# Power.net
KiCad netlist of a schematic drawn in Altium Designer
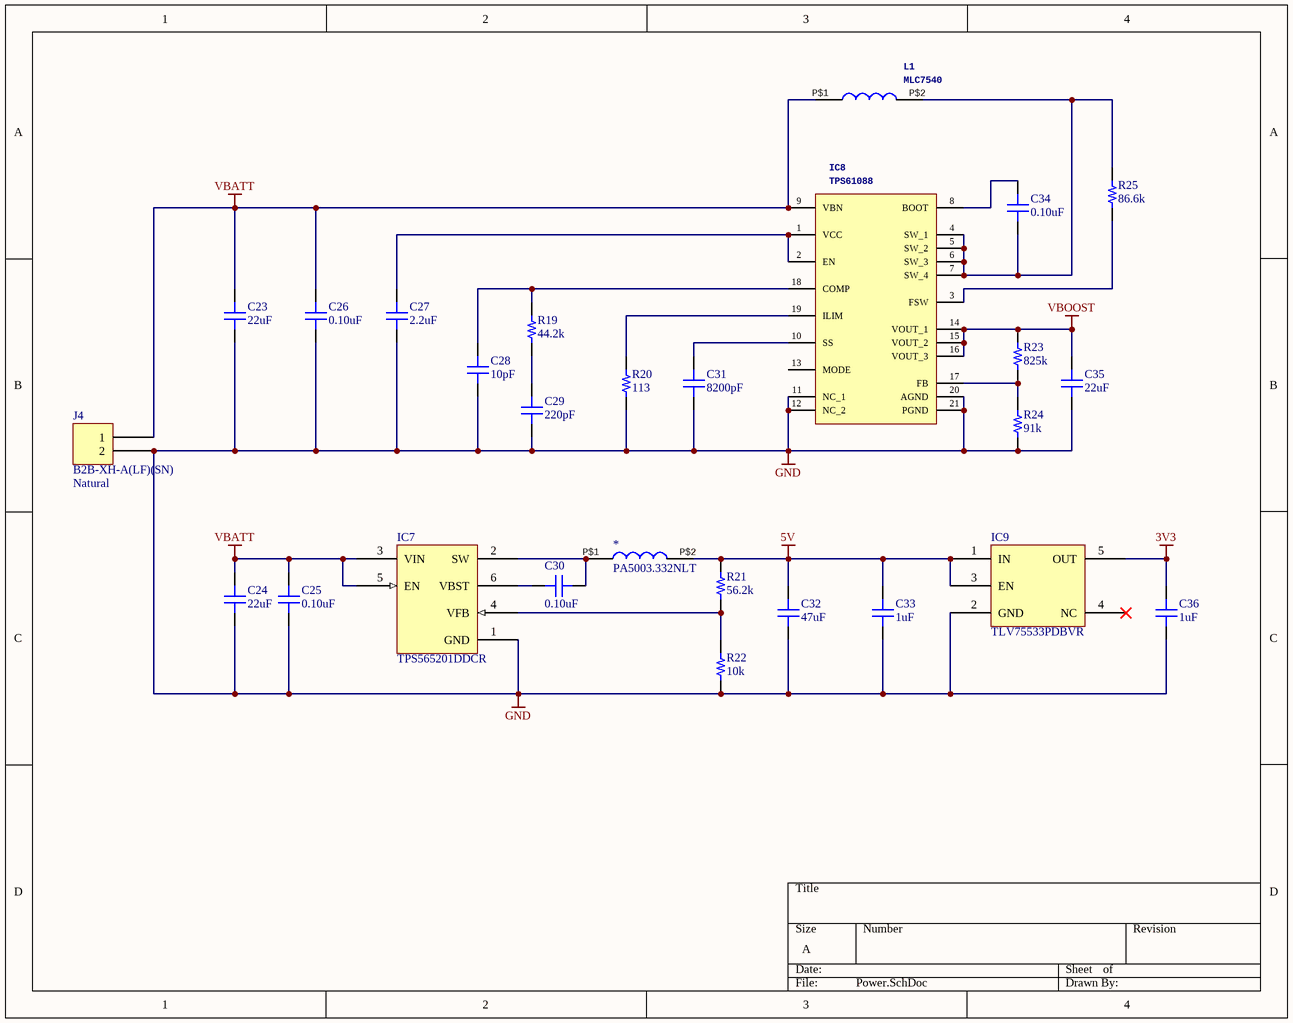
[diagram p0: Power.SchDoc]

(export (version "E")
  (design (tool "Eeschema 10.0.6"))
  (components
    (comp (ref "*")
      (value "PA5003.332NLT")
      (footprint "PA5003")
      (libsource (lib "micromousev2Parts") (part "PA5003.332NLT"))
    )
    (comp (ref "C23")
      (value "22uF")
      (footprint "CAP 1210/3225 - 2.8MM")
      (description "CAP CER 22UF 25V X7R 1210")
      (fields (field (name "PART NUMBER") "TMK325B7226KMHT") (field (name "MANUFACTURER") "Taiyo Yuden"))
      (libsource (lib "Celestial Library Database") (part "Capacitor"))
    )
    (comp (ref "C24")
      (value "22uF")
      (footprint "CAP 0805/2012")
      (description "CAP CER 22UF 16V X5R 0805")
      (fields
        (field (name "PART NUMBER") "CL21A226MOQNNNE")
        (field (name "MANUFACTURER") "Samsung Electro-Mechanics America, Inc.")
      )
      (libsource (lib "Celestial Library Database") (part "Capacitor"))
    )
    (comp (ref "C25")
      (value "0.10uF")
      (footprint "CAP 0402/1005")
      (description "CAP CER 0.1UF 10V X7R 0402")
      (fields
        (field (name "PART NUMBER") "GRM155R71A104KA01D")
        (field (name "MANUFACTURER") "Murata Electronics North America")
      )
      (libsource (lib "Celestial Library Database") (part "Capacitor"))
    )
    (comp (ref "C26")
      (value "0.10uF")
      (footprint "CAP 0603/1608")
      (description "CAP CER 0.1UF 16V X7R 0603")
      (fields (field (name "PART NUMBER") "C0603X104K4RACTU") (field (name "MANUFACTURER") "Kemet"))
      (libsource (lib "Celestial Library Database") (part "Capacitor"))
    )
    (comp (ref "C27")
      (value "2.2uF")
      (footprint "CAP 0603/1608")
      (description "CAP CER 2.2UF 35V X5R 0603")
      (fields
        (field (name "PART NUMBER") "C1608X5R1V225K080AC")
        (field (name "MANUFACTURER") "TDK Corporation")
      )
      (libsource (lib "Celestial Library Database") (part "Capacitor"))
    )
    (comp (ref "C28")
      (value "10pF")
      (footprint "CAP 0402/1005")
      (description "CAP CER 10PF 25V NP0 0402")
      (fields (field (name "PART NUMBER") "C0402C100J3GACTU") (field (name "MANUFACTURER") "Kemet"))
      (libsource (lib "Celestial Library Database") (part "Capacitor"))
    )
    (comp (ref "C29")
      (value "220pF")
      (footprint "CAP 0402/1005")
      (description "CAP CER 220PF 25V NPO 0402")
      (fields (field (name "PART NUMBER") "CC0402JRNPO8BN221") (field (name "MANUFACTURER") "Yageo"))
      (libsource (lib "Celestial Library Database") (part "Capacitor"))
    )
    (comp (ref "C30")
      (value "0.10uF")
      (footprint "CAP 0402/1005")
      (description "CAP CER 0.1UF 10V X7R 0402")
      (fields
        (field (name "PART NUMBER") "GRM155R71E104KE14D")
        (field (name "MANUFACTURER") "Murata Electronics North America")
      )
      (libsource (lib "Celestial Library Database") (part "Capacitor"))
    )
    (comp (ref "C31")
      (value "8200pF")
      (footprint "CAP 0603/1608")
      (description "CAP CER 8200PF 50V X7R 0603")
      (fields
        (field (name "PART NUMBER") "GRM188R71H822KA01D")
        (field (name "MANUFACTURER") "Murata Electronics North America")
      )
      (libsource (lib "Celestial Library Database") (part "Capacitor"))
    )
    (comp (ref "C32")
      (value "47uF")
      (footprint "CAP 1206/3216")
      (description "CAP CER 47UF 10V X5R 1206")
      (fields
        (field (name "PART NUMBER") "CL31A476MPHNNNE")
        (field (name "MANUFACTURER") "Samsung Electro-Mechanics America, Inc.")
      )
      (libsource (lib "Celestial Library Database") (part "Capacitor"))
    )
    (comp (ref "C33")
      (value "1uF")
      (footprint "CAP 0603/1608")
      (description "CAP CER 1UF 10V Y5V 0603")
      (fields
        (field (name "PART NUMBER") "CL10F105ZP8NNNC")
        (field (name "MANUFACTURER") "Samsung Electro-Mechanics America, Inc.")
      )
      (libsource (lib "Celestial Library Database") (part "Capacitor"))
    )
    (comp (ref "C34")
      (value "0.10uF")
      (footprint "CAP 0402/1005")
      (description "CAP CER 0.1UF 16V X5R 0402")
      (fields
        (field (name "PART NUMBER") "GRM155R61C104KA88D")
        (field (name "MANUFACTURER") "Murata Electronics North America")
      )
      (libsource (lib "Celestial Library Database") (part "Capacitor"))
    )
    (comp (ref "C35")
      (value "22uF")
      (footprint "CAP 1210/3225 - 2.8MM")
      (description "CAP CER 22UF 25V X7R 1210")
      (fields (field (name "PART NUMBER") "TMK325B7226KMHT") (field (name "MANUFACTURER") "Taiyo Yuden"))
      (libsource (lib "Celestial Library Database") (part "Capacitor"))
    )
    (comp (ref "C36")
      (value "1uF")
      (footprint "CAP 0603/1608")
      (description "CAP CER 1UF 10V Y5V 0603")
      (fields
        (field (name "PART NUMBER") "CL10F105ZP8NNNC")
        (field (name "MANUFACTURER") "Samsung Electro-Mechanics America, Inc.")
      )
      (libsource (lib "Celestial Library Database") (part "Capacitor"))
    )
    (comp (ref "IC7")
      (value "TPS565201DDCR")
      (footprint "DDC")
      (libsource (lib "micromousev2Parts") (part "TPS565201DDCR"))
    )
    (comp (ref "IC8")
      (value "TPS61088")
      (footprint "RHL(R-PVQFN-N20)_1")
      (fields
        (field (name "ARROW_PART_NUMBER") "TPS61088RHLR")
        (field (name "LIBRARYNAME") "micromousev2Parts")
      )
      (libsource (lib "micromousev2Parts") (part "TPS61088RHLR"))
    )
    (comp (ref "IC9")
      (value "TLV75533PDBVR")
      (footprint "SOT95P280X145-5N")
      (libsource (lib "micromousev2Parts") (part "TLV75533PDBVR"))
    )
    (comp (ref "J4")
      (value "B2B-XH-A(LF)(SN)")
      (footprint "JST XH B2B-XH-A")
      (description "CONN HEADER XH TOP 2POS 2.5MM")
      (fields (field (name "COLOUR") "Natural") (field (name "MANUFACTURER") "JST Sales America Inc."))
      (libsource (lib "Celestial Library Database") (part "2 Pin"))
    )
    (comp (ref "L1")
      (value "MLC7540")
      (footprint "MLC7540")
      (fields (field (name "LIBRARYNAME") "micromousev2Parts"))
      (libsource (lib "micromousev2Parts") (part "MLC7540"))
    )
    (comp (ref "R19")
      (value "44.2k")
      (footprint "RES 0402/1005")
      (description "RES SMD 44.2K OHM 1% 1/10W 0402")
      (fields
        (field (name "PART NUMBER") "ERJ-2RKF4422X")
        (field (name "MANUFACTURER") "Panasonic Electronic Components")
      )
      (libsource (lib "Celestial Library Database") (part "Resistor"))
    )
    (comp (ref "R20")
      (value "113")
      (footprint "RES 0402/1005")
      (description "RES SMD 113 OHM 1% 1/10W 0402")
      (fields
        (field (name "PART NUMBER") "ERJ-2RKF1130X")
        (field (name "MANUFACTURER") "Panasonic Electronic Components")
      )
      (libsource (lib "Celestial Library Database") (part "Resistor"))
    )
    (comp (ref "R21")
      (value "56.2k")
      (footprint "RES 0402/1005")
      (description "RES SMD 0.0OHM JUMPER 1/16W 0402")
      (fields (field (name "PART NUMBER") "RC0402FR-0756K2L") (field (name "MANUFACTURER") "Yageo"))
      (libsource (lib "Celestial Library Database") (part "Resistor"))
    )
    (comp (ref "R22")
      (value "10k")
      (footprint "RES 0402/1005")
      (description "RES SMD 0.0OHM JUMPER 1/16W 0402")
      (fields (field (name "PART NUMBER") "RC0402JR-1310KL") (field (name "MANUFACTURER") "Yageo"))
      (libsource (lib "Celestial Library Database") (part "Resistor"))
    )
    (comp (ref "R23")
      (value "825k")
      (footprint "RES 0402/1005")
      (description "RES SMD 825K OHM 1% 1/10W 0402")
      (fields
        (field (name "PART NUMBER") "ERJ-2RKF8253X")
        (field (name "MANUFACTURER") "Panasonic Electronic Components")
      )
      (libsource (lib "Celestial Library Database") (part "Resistor"))
    )
    (comp (ref "R24")
      (value "91k")
      (footprint "RES 0402/1005")
      (description "RES SMD 91K OHM 1% 1/10W 0402")
      (fields
        (field (name "PART NUMBER") "ERJ-2RKF9102X")
        (field (name "MANUFACTURER") "Panasonic Electronic Components")
      )
      (libsource (lib "Celestial Library Database") (part "Resistor"))
    )
    (comp (ref "R25")
      (value "86.6k")
      (footprint "RES 0402/1005")
      (description "RES SMD 86.6K OHM 1% 1/10W 0402")
      (fields
        (field (name "PART NUMBER") "ERJ-2RKF8662X")
        (field (name "MANUFACTURER") "Panasonic Electronic Components")
      )
      (libsource (lib "Celestial Library Database") (part "Resistor"))
    )
  )
  (nets
    (net (code "1") (name "3V3") (class "Default")
      (node (ref "C36") (pin "2") (pinfunction "2_2") (pintype "passive"))
      (node (ref "IC9") (pin "5") (pinfunction "OUT_5") (pintype "passive"))
    )
    (net (code "2") (name "5V") (class "Default")
      (node (ref "*") (pin "P$2") (pinfunction "2_P$2") (pintype "passive"))
      (node (ref "C32") (pin "2") (pinfunction "2_2") (pintype "passive"))
      (node (ref "C33") (pin "2") (pinfunction "2_2") (pintype "passive"))
      (node (ref "IC9") (pin "1") (pinfunction "IN_1") (pintype "passive"))
      (node (ref "IC9") (pin "3") (pinfunction "EN_3") (pintype "passive"))
      (node (ref "R21") (pin "2") (pinfunction "2_2") (pintype "passive"))
    )
    (net (code "3") (name "GND") (class "Default")
      (node (ref "C23") (pin "1") (pinfunction "1_1") (pintype "passive"))
      (node (ref "C24") (pin "1") (pinfunction "1_1") (pintype "passive"))
      (node (ref "C25") (pin "1") (pinfunction "1_1") (pintype "passive"))
      (node (ref "C26") (pin "1") (pinfunction "1_1") (pintype "passive"))
      (node (ref "C27") (pin "1") (pinfunction "1_1") (pintype "passive"))
      (node (ref "C28") (pin "1") (pinfunction "1_1") (pintype "passive"))
      (node (ref "C29") (pin "1") (pinfunction "1_1") (pintype "passive"))
      (node (ref "C31") (pin "1") (pinfunction "1_1") (pintype "passive"))
      (node (ref "C32") (pin "1") (pinfunction "1_1") (pintype "passive"))
      (node (ref "C33") (pin "1") (pinfunction "1_1") (pintype "passive"))
      (node (ref "C35") (pin "1") (pinfunction "1_1") (pintype "passive"))
      (node (ref "C36") (pin "1") (pinfunction "1_1") (pintype "passive"))
      (node (ref "IC7") (pin "1") (pinfunction "GND_1") (pintype "passive"))
      (node (ref "IC8") (pin "11") (pinfunction "NC_1_11") (pintype "passive"))
      (node (ref "IC8") (pin "12") (pinfunction "NC_2_12") (pintype "passive"))
      (node (ref "IC8") (pin "20") (pinfunction "AGND_20") (pintype "passive"))
      (node (ref "IC8") (pin "21") (pinfunction "PGND_21") (pintype "passive"))
      (node (ref "IC9") (pin "2") (pinfunction "GND_2") (pintype "passive"))
      (node (ref "J4") (pin "2") (pinfunction "2_2") (pintype "passive"))
      (node (ref "R20") (pin "1") (pinfunction "1_1") (pintype "passive"))
      (node (ref "R22") (pin "1") (pinfunction "1_1") (pintype "passive"))
      (node (ref "R24") (pin "1") (pinfunction "1_1") (pintype "passive"))
    )
    (net (code "4") (name "Net-(*-1)") (class "Default")
      (node (ref "*") (pin "P$1") (pinfunction "1_P$1") (pintype "passive"))
      (node (ref "C30") (pin "1") (pinfunction "1_1") (pintype "passive"))
      (node (ref "IC7") (pin "2") (pinfunction "SW_2") (pintype "passive"))
    )
    (net (code "5") (name "Net-(C29-Pad2)") (class "Default")
      (node (ref "C29") (pin "2") (pinfunction "2_2") (pintype "passive"))
      (node (ref "R19") (pin "1") (pinfunction "1_1") (pintype "passive"))
    )
    (net (code "6") (name "Net-(IC7-VBST)") (class "Default")
      (node (ref "C30") (pin "2") (pinfunction "2_2") (pintype "passive"))
      (node (ref "IC7") (pin "6") (pinfunction "VBST_6") (pintype "passive"))
    )
    (net (code "7") (name "Net-(IC7-VFB)") (class "Default")
      (node (ref "IC7") (pin "4") (pinfunction "VFB_4") (pintype "input"))
      (node (ref "R21") (pin "1") (pinfunction "1_1") (pintype "passive"))
      (node (ref "R22") (pin "2") (pinfunction "2_2") (pintype "passive"))
    )
    (net (code "8") (name "Net-(IC8-BOOT)") (class "Default")
      (node (ref "C34") (pin "2") (pinfunction "2_2") (pintype "passive"))
      (node (ref "IC8") (pin "8") (pinfunction "BOOT_8") (pintype "passive"))
    )
    (net (code "9") (name "Net-(IC8-COMP)") (class "Default")
      (node (ref "C28") (pin "2") (pinfunction "2_2") (pintype "passive"))
      (node (ref "IC8") (pin "18") (pinfunction "COMP_18") (pintype "passive"))
      (node (ref "R19") (pin "2") (pinfunction "2_2") (pintype "passive"))
    )
    (net (code "10") (name "Net-(IC8-EN)") (class "Default")
      (node (ref "C27") (pin "2") (pinfunction "2_2") (pintype "passive"))
      (node (ref "IC8") (pin "1") (pinfunction "VCC_1") (pintype "passive"))
      (node (ref "IC8") (pin "2") (pinfunction "EN_2") (pintype "passive"))
    )
    (net (code "11") (name "Net-(IC8-FB)") (class "Default")
      (node (ref "IC8") (pin "17") (pinfunction "FB_17") (pintype "passive"))
      (node (ref "R23") (pin "1") (pinfunction "1_1") (pintype "passive"))
      (node (ref "R24") (pin "2") (pinfunction "2_2") (pintype "passive"))
    )
    (net (code "12") (name "Net-(IC8-FSW)") (class "Default")
      (node (ref "IC8") (pin "3") (pinfunction "FSW_3") (pintype "passive"))
      (node (ref "R25") (pin "1") (pinfunction "1_1") (pintype "passive"))
    )
    (net (code "13") (name "Net-(IC8-ILIM)") (class "Default")
      (node (ref "IC8") (pin "19") (pinfunction "ILIM_19") (pintype "passive"))
      (node (ref "R20") (pin "2") (pinfunction "2_2") (pintype "passive"))
    )
    (net (code "14") (name "Net-(IC8-SS)") (class "Default")
      (node (ref "C31") (pin "2") (pinfunction "2_2") (pintype "passive"))
      (node (ref "IC8") (pin "10") (pinfunction "SS_10") (pintype "passive"))
    )
    (net (code "15") (name "Net-(IC8-SW_1)") (class "Default")
      (node (ref "C34") (pin "1") (pinfunction "1_1") (pintype "passive"))
      (node (ref "IC8") (pin "4") (pinfunction "SW_1_4") (pintype "passive"))
      (node (ref "IC8") (pin "5") (pinfunction "SW_2_5") (pintype "passive"))
      (node (ref "IC8") (pin "6") (pinfunction "SW_3_6") (pintype "passive"))
      (node (ref "IC8") (pin "7") (pinfunction "SW_4_7") (pintype "passive"))
      (node (ref "L1") (pin "P$2") (pinfunction "2_P$2") (pintype "passive"))
      (node (ref "R25") (pin "2") (pinfunction "2_2") (pintype "passive"))
    )
    (net (code "16") (name "VBATT") (class "Default")
      (node (ref "C23") (pin "2") (pinfunction "2_2") (pintype "passive"))
      (node (ref "C24") (pin "2") (pinfunction "2_2") (pintype "passive"))
      (node (ref "C25") (pin "2") (pinfunction "2_2") (pintype "passive"))
      (node (ref "C26") (pin "2") (pinfunction "2_2") (pintype "passive"))
      (node (ref "IC7") (pin "3") (pinfunction "VIN_3") (pintype "passive"))
      (node (ref "IC7") (pin "5") (pinfunction "EN_5") (pintype "input"))
      (node (ref "IC8") (pin "9") (pinfunction "VBN_9") (pintype "passive"))
      (node (ref "J4") (pin "1") (pinfunction "1_1") (pintype "passive"))
      (node (ref "L1") (pin "P$1") (pinfunction "1_P$1") (pintype "passive"))
    )
    (net (code "17") (name "VBOOST") (class "Default")
      (node (ref "C35") (pin "2") (pinfunction "2_2") (pintype "passive"))
      (node (ref "IC8") (pin "14") (pinfunction "VOUT_1_14") (pintype "passive"))
      (node (ref "IC8") (pin "15") (pinfunction "VOUT_2_15") (pintype "passive"))
      (node (ref "IC8") (pin "16") (pinfunction "VOUT_3_16") (pintype "passive"))
      (node (ref "R23") (pin "2") (pinfunction "2_2") (pintype "passive"))
    )
    (net (code "18") (name "unconnected-(IC8-MODE-Pad13)") (class "Default")
      (node (ref "IC8") (pin "13") (pinfunction "MODE_13") (pintype "passive"))
    )
    (net (code "19") (name "unconnected-(IC9-NC-Pad4)") (class "Default")
      (node (ref "IC9") (pin "4") (pinfunction "NC_4") (pintype "passive+no_connect"))
    )
  )
)
